# Amplifier.net
KiCad netlist of a schematic drawn in Altium Designer
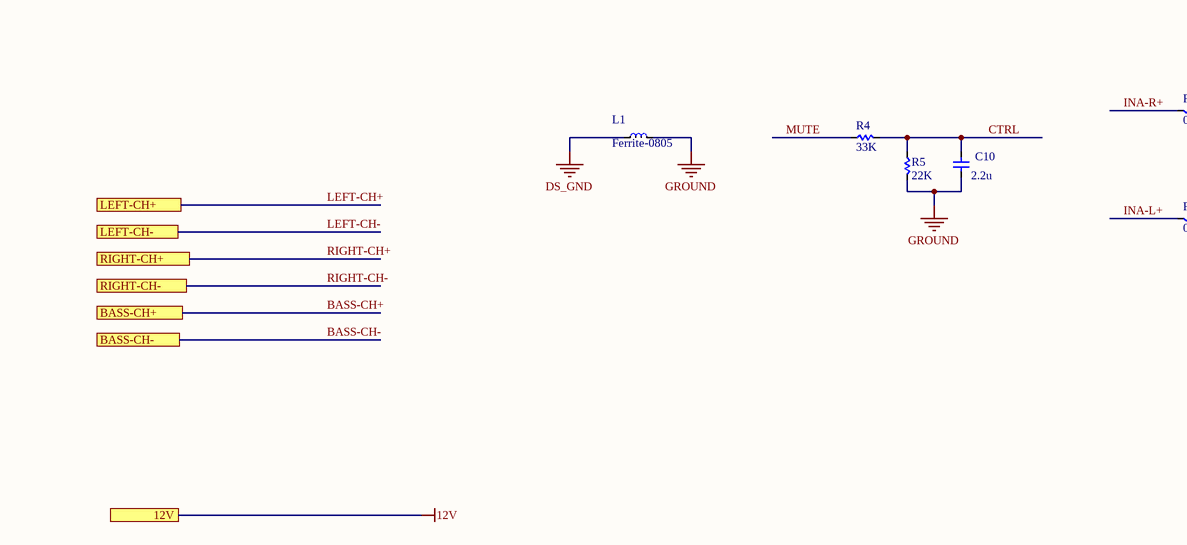
[diagram p0: Amplifier.SchDoc, top left]
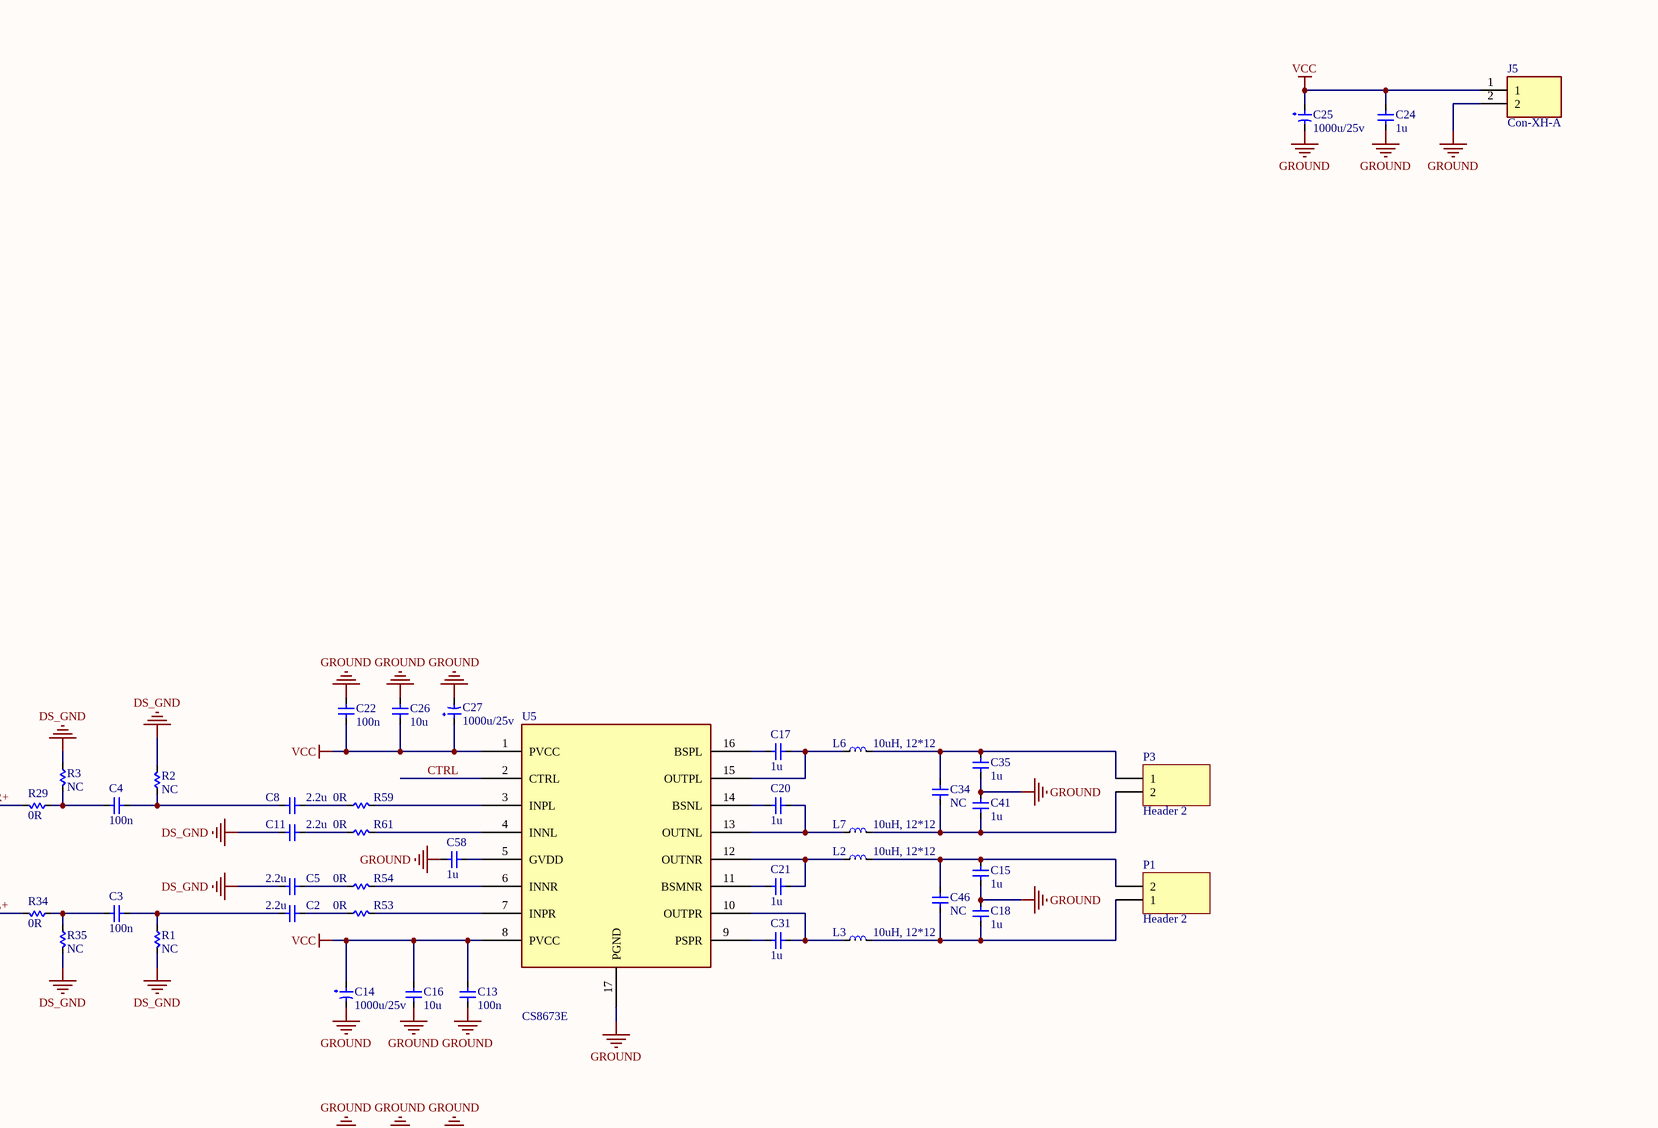
[diagram p1: Amplifier.SchDoc, top right]
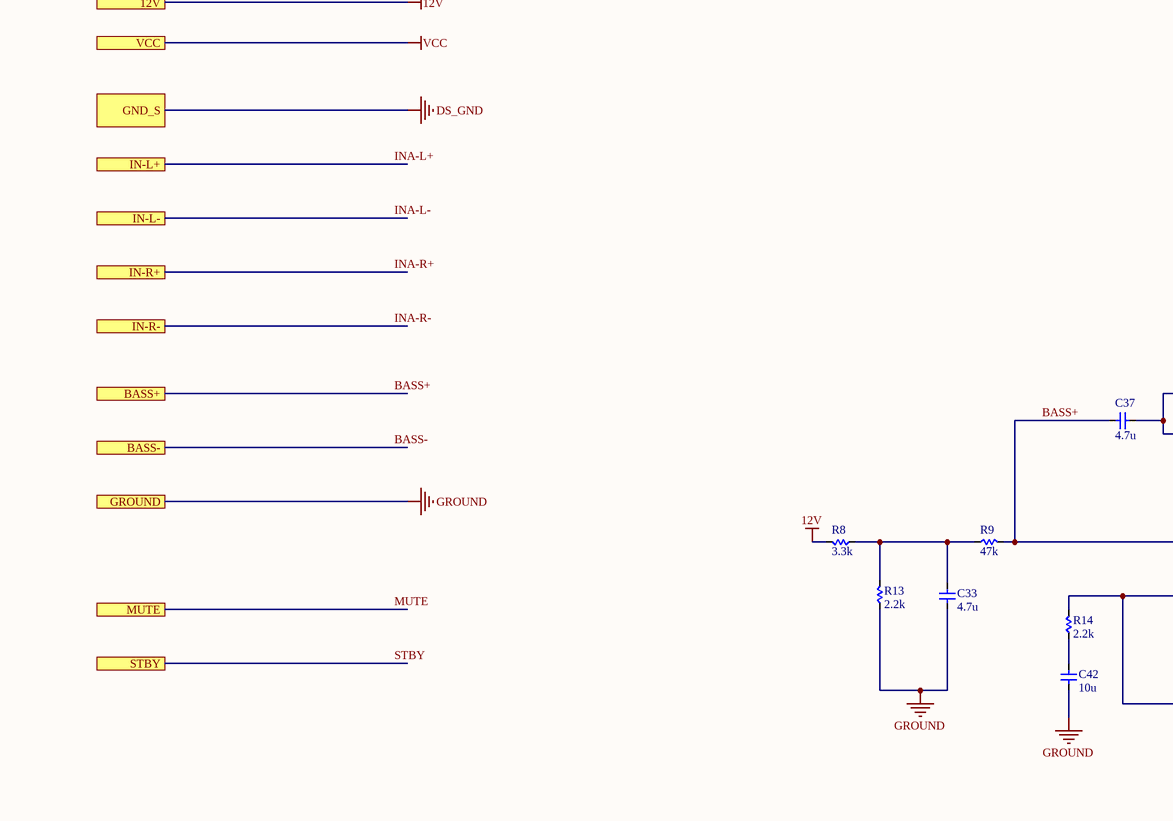
[diagram p2: Amplifier.SchDoc, bottom left]
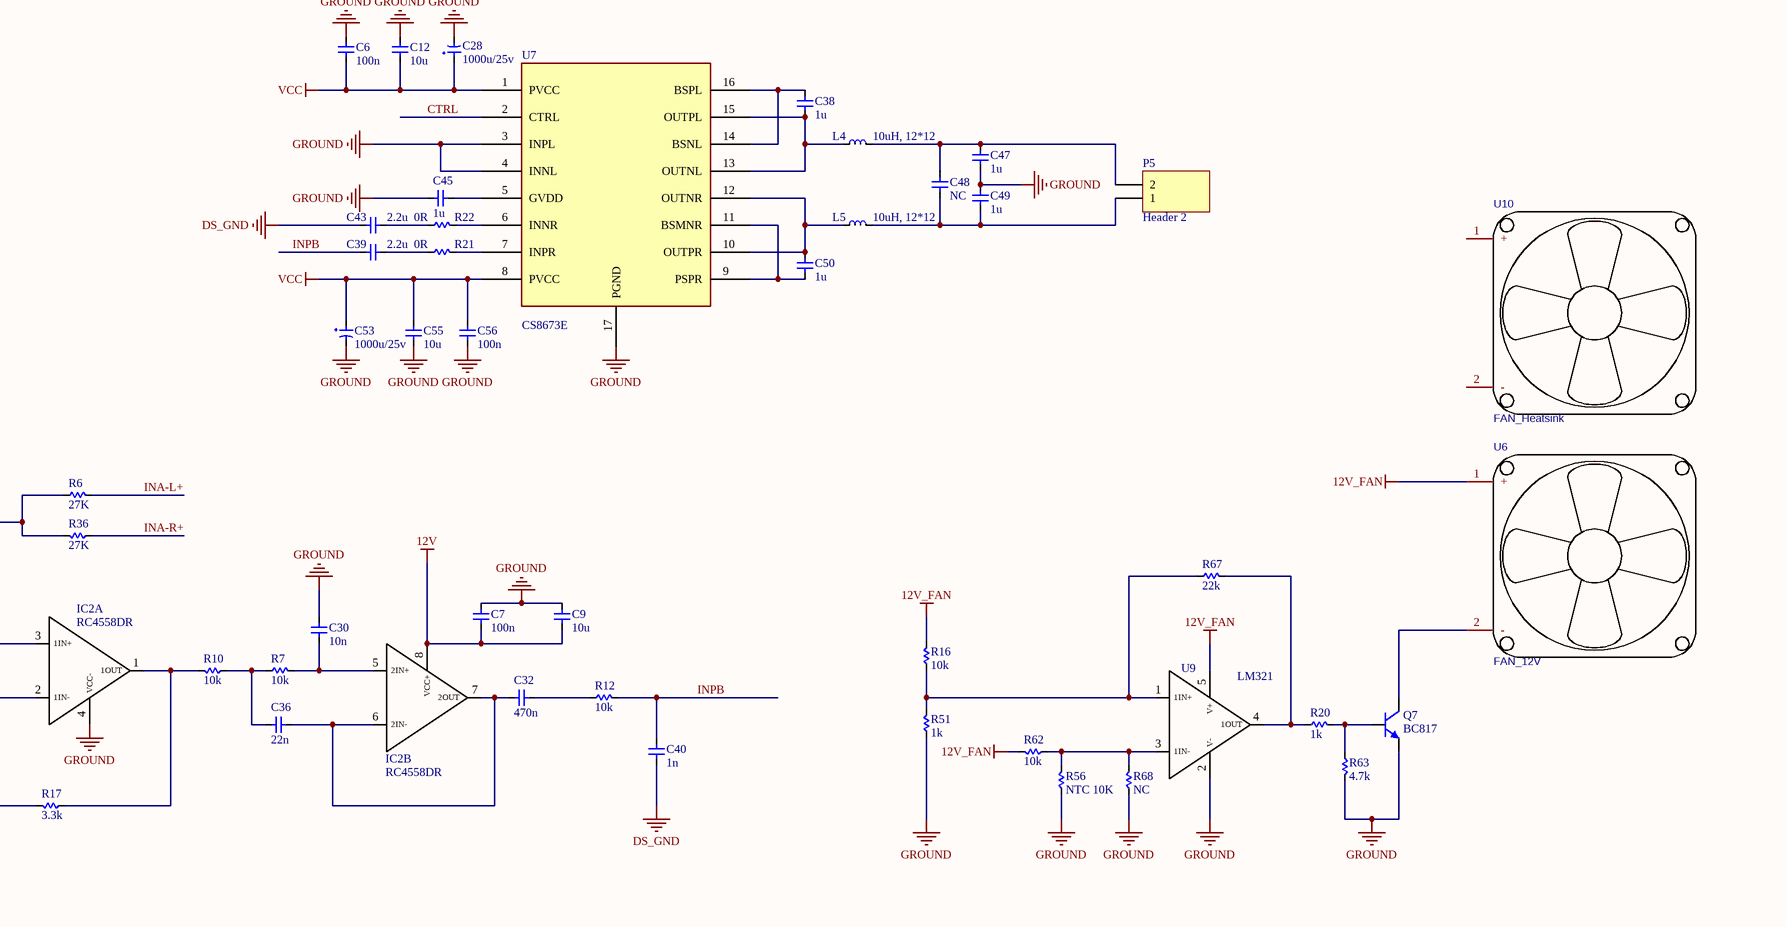
[diagram p3: Amplifier.SchDoc, bottom right]

(export (version "E")
  (design (tool "Eeschema 10.0.6"))
  (components
    (comp (ref "C2")
      (value "2.2u")
      (footprint "cap0603")
      (description "Capacitor 0603")
      (fields (field (name "PUBLISHER") "Altium Limited"))
      (libsource (lib "mylib1") (part "Cap 0603"))
    )
    (comp (ref "C3")
      (value "100n")
      (footprint "cap0603")
      (description "Capacitor 0603")
      (fields (field (name "PUBLISHER") "Altium Limited"))
      (libsource (lib "mylib") (part "Cap 0603"))
    )
    (comp (ref "C4")
      (value "100n")
      (footprint "cap0603")
      (description "Capacitor 0603")
      (fields (field (name "PUBLISHER") "Altium Limited"))
      (libsource (lib "mylib") (part "Cap 0603"))
    )
    (comp (ref "C5")
      (value "2.2u")
      (footprint "cap0603")
      (description "Capacitor 0603")
      (fields (field (name "PUBLISHER") "Altium Limited"))
      (libsource (lib "mylib1") (part "Cap 0603"))
    )
    (comp (ref "C6")
      (value "100n")
      (footprint "cap0603")
      (description "Capacitor 0603")
      (fields (field (name "PUBLISHER") "Altium Limited"))
      (libsource (lib "mylib1") (part "Cap 0603"))
    )
    (comp (ref "C7")
      (value "100n")
      (footprint "cap0603")
      (description "Capacitor 0603")
      (fields (field (name "PUBLISHER") "Altium Limited"))
      (libsource (lib "mylib1") (part "Cap 0603"))
    )
    (comp (ref "C8")
      (value "2.2u")
      (footprint "cap0603")
      (description "Capacitor 0603")
      (fields (field (name "PUBLISHER") "Altium Limited"))
      (libsource (lib "mylib1") (part "Cap 0603"))
    )
    (comp (ref "C9")
      (value "10u")
      (footprint "CAP 0805")
      (description "Capacitor 0805")
      (fields (field (name "PUBLISHER") "Altium Limited"))
      (libsource (lib "Amin-Library") (part "Cap 0805"))
    )
    (comp (ref "C10")
      (value "2.2u")
      (footprint "cap0603")
      (description "Capacitor 0603")
      (fields (field (name "PUBLISHER") "Altium Limited"))
      (libsource (lib "mylib") (part "Cap 0603"))
    )
    (comp (ref "C11")
      (value "2.2u")
      (footprint "cap0603")
      (description "Capacitor 0603")
      (fields (field (name "PUBLISHER") "Altium Limited"))
      (libsource (lib "mylib1") (part "Cap 0603"))
    )
    (comp (ref "C12")
      (value "10u")
      (footprint "CAP 0805")
      (description "Capacitor 0805")
      (fields (field (name "PUBLISHER") "Altium Limited"))
      (libsource (lib "Amin-Library") (part "Cap 0805"))
    )
    (comp (ref "C13")
      (value "100n")
      (footprint "cap0603")
      (description "Capacitor 0603")
      (fields (field (name "PUBLISHER") "Altium Limited"))
      (libsource (lib "mylib1") (part "Cap 0603"))
    )
    (comp (ref "C14")
      (value "1000u/25v")
      (footprint "CAP DIP 10*13")
      (description "2200ÂµF 50V Aluminum Electrolytic Capacitors Radial, Can 1000 Hrs @ 105Â°C")
      (fields (field (name "MF") "Nichicon") (field (name "MP") "UVZ1H222MHD"))
      (libsource (lib "") (part "capacitor dip 10*13_1"))
    )
    (comp (ref "C15")
      (value "1u")
      (footprint "CAP 0805")
      (description "Capacitor 0805")
      (fields (field (name "PUBLISHER") "Altium Limited"))
      (libsource (lib "Amin-Library") (part "Cap 0805"))
    )
    (comp (ref "C16")
      (value "10u")
      (footprint "CAP 0805")
      (description "Capacitor 0805")
      (fields (field (name "PUBLISHER") "Altium Limited"))
      (libsource (lib "Amin-Library") (part "Cap 0805"))
    )
    (comp (ref "C17")
      (value "1u")
      (footprint "CAP 0805")
      (description "Capacitor 0805")
      (fields (field (name "PUBLISHER") "Altium Limited"))
      (libsource (lib "Amin-Library") (part "Cap 0805"))
    )
    (comp (ref "C18")
      (value "1u")
      (footprint "CAP 0805")
      (description "Capacitor 0805")
      (fields (field (name "PUBLISHER") "Altium Limited"))
      (libsource (lib "Amin-Library") (part "Cap 0805"))
    )
    (comp (ref "C20")
      (value "1u")
      (footprint "CAP 0805")
      (description "Capacitor 0805")
      (fields (field (name "PUBLISHER") "Altium Limited"))
      (libsource (lib "Amin-Library") (part "Cap 0805"))
    )
    (comp (ref "C21")
      (value "1u")
      (footprint "CAP 0805")
      (description "Capacitor 0805")
      (fields (field (name "PUBLISHER") "Altium Limited"))
      (libsource (lib "Amin-Library") (part "Cap 0805"))
    )
    (comp (ref "C22")
      (value "100n")
      (footprint "cap0603")
      (description "Capacitor 0603")
      (fields (field (name "PUBLISHER") "Altium Limited"))
      (libsource (lib "mylib1") (part "Cap 0603"))
    )
    (comp (ref "C24")
      (value "1u")
      (footprint "cap0603")
      (description "Capacitor 0603")
      (fields (field (name "PUBLISHER") "Altium Limited"))
      (libsource (lib "mylib1") (part "Cap 0603"))
    )
    (comp (ref "C25")
      (value "1000u/25v")
      (footprint "CAP DIP 10*13")
      (description "2200ÂµF 50V Aluminum Electrolytic Capacitors Radial, Can 1000 Hrs @ 105Â°C")
      (fields (field (name "MF") "Nichicon") (field (name "MP") "UVZ1H222MHD"))
      (libsource (lib "") (part "capacitor dip 10*13_1"))
    )
    (comp (ref "C26")
      (value "10u")
      (footprint "CAP 0805")
      (description "Capacitor 0805")
      (fields (field (name "PUBLISHER") "Altium Limited"))
      (libsource (lib "Amin-Library") (part "Cap 0805"))
    )
    (comp (ref "C27")
      (value "1000u/25v")
      (footprint "CAP DIP 10*13")
      (description "2200ÂµF 50V Aluminum Electrolytic Capacitors Radial, Can 1000 Hrs @ 105Â°C")
      (fields (field (name "MF") "Nichicon") (field (name "MP") "UVZ1H222MHD"))
      (libsource (lib "mylib1") (part "capacitor dip 10*13"))
    )
    (comp (ref "C28")
      (value "1000u/25v")
      (footprint "CAP DIP 10*13")
      (description "2200ÂµF 50V Aluminum Electrolytic Capacitors Radial, Can 1000 Hrs @ 105Â°C")
      (fields (field (name "MF") "Nichicon") (field (name "MP") "UVZ1H222MHD"))
      (libsource (lib "mylib1") (part "capacitor dip 10*13"))
    )
    (comp (ref "C30")
      (value "10n")
      (footprint "cap0603")
      (description "Capacitor 0603")
      (fields (field (name "PUBLISHER") "Altium Limited"))
      (libsource (lib "mylib1") (part "Cap 0603"))
    )
    (comp (ref "C31")
      (value "1u")
      (footprint "CAP 0805")
      (description "Capacitor 0805")
      (fields (field (name "PUBLISHER") "Altium Limited"))
      (libsource (lib "Amin-Library") (part "Cap 0805"))
    )
    (comp (ref "C32")
      (value "470n")
      (footprint "cap0603")
      (description "Capacitor 0603")
      (fields (field (name "PUBLISHER") "Altium Limited"))
      (libsource (lib "mylib1") (part "Cap 0603"))
    )
    (comp (ref "C33")
      (value "4.7u")
      (footprint "cap0603")
      (description "Capacitor 0603")
      (fields (field (name "PUBLISHER") "Altium Limited"))
      (libsource (lib "mylib") (part "Cap 0603"))
    )
    (comp (ref "C34")
      (value "NC")
      (footprint "CAP 0805")
      (description "Capacitor 0805")
      (fields (field (name "PUBLISHER") "Altium Limited"))
      (libsource (lib "Amin-Library") (part "Cap 0805"))
    )
    (comp (ref "C35")
      (value "1u")
      (footprint "CAP 0805")
      (description "Capacitor 0805")
      (fields (field (name "PUBLISHER") "Altium Limited"))
      (libsource (lib "Amin-Library") (part "Cap 0805"))
    )
    (comp (ref "C36")
      (value "22n")
      (footprint "cap0603")
      (description "Capacitor 0603")
      (fields (field (name "PUBLISHER") "Altium Limited"))
      (libsource (lib "mylib1") (part "Cap 0603"))
    )
    (comp (ref "C37")
      (value "4.7u")
      (footprint "cap0603")
      (description "Capacitor 0603")
      (fields (field (name "PUBLISHER") "Altium Limited"))
      (libsource (lib "mylib") (part "Cap 0603"))
    )
    (comp (ref "C38")
      (value "1u")
      (footprint "CAP 0805")
      (description "Capacitor 0805")
      (fields (field (name "PUBLISHER") "Altium Limited"))
      (libsource (lib "Amin-Library") (part "Cap 0805"))
    )
    (comp (ref "C39")
      (value "2.2u")
      (footprint "cap0603")
      (description "Capacitor 0603")
      (fields (field (name "PUBLISHER") "Altium Limited"))
      (libsource (lib "mylib1") (part "Cap 0603"))
    )
    (comp (ref "C40")
      (value "1n")
      (footprint "cap0603")
      (description "Capacitor 0603")
      (fields (field (name "PUBLISHER") "Altium Limited"))
      (libsource (lib "mylib1") (part "Cap 0603"))
    )
    (comp (ref "C41")
      (value "1u")
      (footprint "CAP 0805")
      (description "Capacitor 0805")
      (fields (field (name "PUBLISHER") "Altium Limited"))
      (libsource (lib "Amin-Library") (part "Cap 0805"))
    )
    (comp (ref "C42")
      (value "10u")
      (footprint "CAP 1206")
      (description "Capacitor 1206")
      (fields (field (name "PUBLISHER") "Altium Limited"))
      (libsource (lib "mylib") (part "Cap 1206"))
    )
    (comp (ref "C43")
      (value "2.2u")
      (footprint "cap0603")
      (description "Capacitor 0603")
      (fields (field (name "PUBLISHER") "Altium Limited"))
      (libsource (lib "mylib1") (part "Cap 0603"))
    )
    (comp (ref "C45")
      (value "1u")
      (footprint "cap0603")
      (description "Capacitor 0603")
      (fields (field (name "PUBLISHER") "Altium Limited"))
      (libsource (lib "mylib1") (part "Cap 0603"))
    )
    (comp (ref "C46")
      (value "NC")
      (footprint "CAP 0805")
      (description "Capacitor 0805")
      (fields (field (name "PUBLISHER") "Altium Limited"))
      (libsource (lib "Amin-Library") (part "Cap 0805"))
    )
    (comp (ref "C47")
      (value "1u")
      (footprint "CAP 0805")
      (description "Capacitor 0805")
      (fields (field (name "PUBLISHER") "Altium Limited"))
      (libsource (lib "Amin-Library") (part "Cap 0805"))
    )
    (comp (ref "C48")
      (value "NC")
      (footprint "CAP 0805")
      (description "Capacitor 0805")
      (fields (field (name "PUBLISHER") "Altium Limited"))
      (libsource (lib "Amin-Library") (part "Cap 0805"))
    )
    (comp (ref "C49")
      (value "1u")
      (footprint "CAP 0805")
      (description "Capacitor 0805")
      (fields (field (name "PUBLISHER") "Altium Limited"))
      (libsource (lib "Amin-Library") (part "Cap 0805"))
    )
    (comp (ref "C50")
      (value "1u")
      (footprint "CAP 0805")
      (description "Capacitor 0805")
      (fields (field (name "PUBLISHER") "Altium Limited"))
      (libsource (lib "Amin-Library") (part "Cap 0805"))
    )
    (comp (ref "C53")
      (value "1000u/25v")
      (footprint "CAP DIP 10*13")
      (description "2200ÂµF 50V Aluminum Electrolytic Capacitors Radial, Can 1000 Hrs @ 105Â°C")
      (fields (field (name "MF") "Nichicon") (field (name "MP") "UVZ1H222MHD"))
      (libsource (lib "") (part "capacitor dip 10*13_1"))
    )
    (comp (ref "C55")
      (value "10u")
      (footprint "CAP 0805")
      (description "Capacitor 0805")
      (fields (field (name "PUBLISHER") "Altium Limited"))
      (libsource (lib "Amin-Library") (part "Cap 0805"))
    )
    (comp (ref "C56")
      (value "100n")
      (footprint "cap0603")
      (description "Capacitor 0603")
      (fields (field (name "PUBLISHER") "Altium Limited"))
      (libsource (lib "mylib1") (part "Cap 0603"))
    )
    (comp (ref "C58")
      (value "1u")
      (footprint "cap0603")
      (description "Capacitor 0603")
      (fields (field (name "PUBLISHER") "Altium Limited"))
      (libsource (lib "mylib1") (part "Cap 0603"))
    )
    (comp (ref "IC2")
      (value "RC4558DR")
      (footprint "RC4558")
      (description "Integrated Circuit SOIC 8")
      (fields (field (name "MOUSER PART NUMBER") "595-RC4558DR"))
      (libsource (lib "STM32F103C8T6") (part "RC4558DR"))
    )
    (comp (ref "J5")
      (value "Con-XH-A")
      (footprint "Con-JST_B2B-XH-A")
      (description "Connector Header Through Hole 2 position 0.098 _2.50mm_")
      (fields (field (name "MP") "B2B-XH-A_LF__SN_") (field (name "MF") "JST Sales"))
      (libsource (lib "Amin-Library") (part "Con-B2B-XH-A"))
    )
    (comp (ref "L1")
      (value "Ferrite-0805")
      (footprint "Ferrite-0805")
      (description "BLM Series 0805 330 Ohm 400 mA 0.58 Ohm DCR Surface Mount Ferrite Bead")
      (fields (field (name "MF") "Murata") (field (name "MP") "BLM18BB331SN1D"))
      (libsource (lib "mylib") (part "Ferrite _0805"))
    )
    (comp (ref "L2")
      (value "10uH, 12*12")
      (footprint "inductor 12*12")
      (description "Inductor round 12*12")
      (fields (field (name "MP") "DR127-330-R") (field (name "MF") "Eaton"))
      (libsource (lib "Amin-Library") (part "INDUCTOR 12*12"))
    )
    (comp (ref "L3")
      (value "10uH, 12*12")
      (footprint "inductor 12*12")
      (description "Inductor round 12*12")
      (fields (field (name "MP") "DR127-330-R") (field (name "MF") "Eaton"))
      (libsource (lib "Amin-Library") (part "INDUCTOR 12*12"))
    )
    (comp (ref "L4")
      (value "10uH, 12*12")
      (footprint "inductor 12*12")
      (description "Inductor round 12*12")
      (fields (field (name "MP") "DR127-330-R") (field (name "MF") "Eaton"))
      (libsource (lib "Amin-Library") (part "INDUCTOR 12*12"))
    )
    (comp (ref "L5")
      (value "10uH, 12*12")
      (footprint "inductor 12*12")
      (description "Inductor round 12*12")
      (fields (field (name "MP") "DR127-330-R") (field (name "MF") "Eaton"))
      (libsource (lib "Amin-Library") (part "INDUCTOR 12*12"))
    )
    (comp (ref "L6")
      (value "10uH, 12*12")
      (footprint "inductor 12*12")
      (description "Inductor round 12*12")
      (fields (field (name "MP") "DR127-330-R") (field (name "MF") "Eaton"))
      (libsource (lib "Amin-Library") (part "INDUCTOR 12*12"))
    )
    (comp (ref "L7")
      (value "10uH, 12*12")
      (footprint "inductor 12*12")
      (description "Inductor round 12*12")
      (fields (field (name "MP") "DR127-330-R") (field (name "MF") "Eaton"))
      (libsource (lib "Amin-Library") (part "INDUCTOR 12*12"))
    )
    (comp (ref "P1")
      (value "Header 2")
      (footprint "CONN-PHOENIX-5.08")
      (description "Phoenix Connector 5.08")
      (fields (field (name "PUBLISHER") "Altium Limited"))
      (libsource (lib "") (part "CONN-Phoenix-5.08_1"))
    )
    (comp (ref "P3")
      (value "Header 2")
      (footprint "CONN-PHOENIX-5.08")
      (description "Phoenix Connector 5.08")
      (fields (field (name "PUBLISHER") "Altium Limited"))
      (libsource (lib "Amin-Library") (part "CONN-Phoenix-5.08"))
    )
    (comp (ref "P5")
      (value "Header 2")
      (footprint "CONN-PHOENIX-5.08")
      (description "Phoenix Connector 5.08")
      (fields (field (name "PUBLISHER") "Altium Limited"))
      (libsource (lib "") (part "CONN-Phoenix-5.08_1"))
    )
    (comp (ref "Q7")
      (value "BC817")
      (footprint "BC817")
      (description "NPN General Purpose Amplifier BJT")
      (fields (field (name "PUBLISHER") "Altium Limited"))
      (libsource (lib "Amin-Library") (part "BC817"))
    )
    (comp (ref "R1")
      (value "NC")
      (footprint "RES-0603")
      (description "Resistor 0603")
      (fields (field (name "PUBLISHER") "Altium Limited"))
      (libsource (lib "mylib1") (part "Res 0603"))
    )
    (comp (ref "R2")
      (value "NC")
      (footprint "RES-0603")
      (description "Resistor 0603")
      (fields (field (name "PUBLISHER") "Altium Limited"))
      (libsource (lib "mylib1") (part "Res 0603"))
    )
    (comp (ref "R3")
      (value "NC")
      (footprint "RES-0603")
      (description "Resistor 0603")
      (fields (field (name "PUBLISHER") "Altium Limited"))
      (libsource (lib "mylib1") (part "Res 0603"))
    )
    (comp (ref "R4")
      (value "33K")
      (footprint "RES-0603")
      (description "Resistor 0603")
      (fields (field (name "PUBLISHER") "Altium Limited"))
      (libsource (lib "mylib1") (part "Res 0603"))
    )
    (comp (ref "R5")
      (value "22K")
      (footprint "RES-0603")
      (description "Resistor 0603")
      (fields (field (name "PUBLISHER") "Altium Limited"))
      (libsource (lib "mylib1") (part "Res 0603"))
    )
    (comp (ref "R6")
      (value "27K")
      (footprint "RES-0603")
      (description "Resistor 0603")
      (fields (field (name "PUBLISHER") "Altium Limited"))
      (libsource (lib "mylib1") (part "Res 0603"))
    )
    (comp (ref "R7")
      (value "10k")
      (footprint "RES-0603")
      (description "Resistor 0603")
      (fields (field (name "PUBLISHER") "Altium Limited"))
      (libsource (lib "mylib1") (part "Res 0603"))
    )
    (comp (ref "R8")
      (value "3.3k")
      (footprint "RES-0603")
      (description "Resistor 0603")
      (fields (field (name "PUBLISHER") "Altium Limited"))
      (libsource (lib "mylib1") (part "Res 0603"))
    )
    (comp (ref "R9")
      (value "47k")
      (footprint "RES-0603")
      (description "Resistor 0603")
      (fields (field (name "PUBLISHER") "Altium Limited"))
      (libsource (lib "mylib1") (part "Res 0603"))
    )
    (comp (ref "R10")
      (value "10k")
      (footprint "RES-0603")
      (description "Resistor 0603")
      (fields (field (name "PUBLISHER") "Altium Limited"))
      (libsource (lib "mylib1") (part "Res 0603"))
    )
    (comp (ref "R12")
      (value "10k")
      (footprint "RES-0603")
      (description "Resistor 0603")
      (fields (field (name "PUBLISHER") "Altium Limited"))
      (libsource (lib "mylib1") (part "Res 0603"))
    )
    (comp (ref "R13")
      (value "2.2k")
      (footprint "RES-0603")
      (description "Resistor 0603")
      (fields (field (name "PUBLISHER") "Altium Limited"))
      (libsource (lib "mylib1") (part "Res 0603"))
    )
    (comp (ref "R14")
      (value "2.2k")
      (footprint "RES-0603")
      (description "Resistor 0603")
      (fields (field (name "PUBLISHER") "Altium Limited"))
      (libsource (lib "mylib1") (part "Res 0603"))
    )
    (comp (ref "R16")
      (value "10k")
      (footprint "RES-0603")
      (description "Resistor 0603")
      (fields (field (name "PUBLISHER") "Altium Limited"))
      (libsource (lib "Amin-Library") (part "Res 0603"))
    )
    (comp (ref "R17")
      (value "3.3k")
      (footprint "RES-0603")
      (description "Resistor 0603")
      (fields (field (name "PUBLISHER") "Altium Limited"))
      (libsource (lib "mylib1") (part "Res 0603"))
    )
    (comp (ref "R20")
      (value "1k")
      (footprint "RES-0603")
      (description "Resistor 0603")
      (fields (field (name "PUBLISHER") "Altium Limited"))
      (libsource (lib "Amin-Library") (part "Res 0603"))
    )
    (comp (ref "R21")
      (value "0R")
      (footprint "RES-0603")
      (description "Resistor 0603")
      (fields (field (name "PUBLISHER") "Altium Limited"))
      (libsource (lib "Amin-Library") (part "Res 0603"))
    )
    (comp (ref "R22")
      (value "0R")
      (footprint "RES-0603")
      (description "Resistor 0603")
      (fields (field (name "PUBLISHER") "Altium Limited"))
      (libsource (lib "Amin-Library") (part "Res 0603"))
    )
    (comp (ref "R29")
      (value "0R")
      (footprint "RES-0603")
      (description "Resistor 0603")
      (fields (field (name "PUBLISHER") "Altium Limited"))
      (libsource (lib "mylib1") (part "Res 0603"))
    )
    (comp (ref "R34")
      (value "0R")
      (footprint "RES-0603")
      (description "Resistor 0603")
      (fields (field (name "PUBLISHER") "Altium Limited"))
      (libsource (lib "mylib1") (part "Res 0603"))
    )
    (comp (ref "R35")
      (value "NC")
      (footprint "RES-0603")
      (description "Resistor 0603")
      (fields (field (name "PUBLISHER") "Altium Limited"))
      (libsource (lib "mylib1") (part "Res 0603"))
    )
    (comp (ref "R36")
      (value "27K")
      (footprint "RES-0603")
      (description "Resistor 0603")
      (fields (field (name "PUBLISHER") "Altium Limited"))
      (libsource (lib "mylib1") (part "Res 0603"))
    )
    (comp (ref "R51")
      (value "1k")
      (footprint "RES-0603")
      (description "Resistor 0603")
      (fields (field (name "PUBLISHER") "Altium Limited"))
      (libsource (lib "Amin-Library") (part "Res 0603"))
    )
    (comp (ref "R53")
      (value "0R")
      (footprint "RES-0603")
      (description "Resistor 0603")
      (fields (field (name "PUBLISHER") "Altium Limited"))
      (libsource (lib "Amin-Library") (part "Res 0603"))
    )
    (comp (ref "R54")
      (value "0R")
      (footprint "RES-0603")
      (description "Resistor 0603")
      (fields (field (name "PUBLISHER") "Altium Limited"))
      (libsource (lib "Amin-Library") (part "Res 0603"))
    )
    (comp (ref "R56")
      (value "NTC 10K")
      (footprint "RES-0805")
      (description "resistor 0805")
      (libsource (lib "Amin-Library") (part "Res 0805"))
    )
    (comp (ref "R59")
      (value "0R")
      (footprint "RES-0603")
      (description "Resistor 0603")
      (fields (field (name "PUBLISHER") "Altium Limited"))
      (libsource (lib "Amin-Library") (part "Res 0603"))
    )
    (comp (ref "R61")
      (value "0R")
      (footprint "RES-0603")
      (description "Resistor 0603")
      (fields (field (name "PUBLISHER") "Altium Limited"))
      (libsource (lib "Amin-Library") (part "Res 0603"))
    )
    (comp (ref "R62")
      (value "10k")
      (footprint "RES-0603")
      (description "Resistor 0603")
      (fields (field (name "PUBLISHER") "Altium Limited"))
      (libsource (lib "Amin-Library") (part "Res 0603"))
    )
    (comp (ref "R63")
      (value "4.7k")
      (footprint "RES-0603")
      (description "Resistor 0603")
      (fields (field (name "PUBLISHER") "Altium Limited"))
      (libsource (lib "Amin-Library") (part "Res 0603"))
    )
    (comp (ref "R67")
      (value "22k")
      (footprint "RES-0603")
      (description "Resistor 0603")
      (fields (field (name "PUBLISHER") "Altium Limited"))
      (libsource (lib "Amin-Library") (part "Res 0603"))
    )
    (comp (ref "R68")
      (value "NC")
      (footprint "RES-0805")
      (description "resistor 0805")
      (libsource (lib "Amin-Library") (part "Res 0805"))
    )
    (comp (ref "U5")
      (value "CS8673E")
      (footprint "CS8673E")
      (description "AB/D 2X40W BTL & 80W PBTL ESOP16")
      (fields
        (field (name "MANUFACTURER_PART_NUMBER") "CS8679E")
        (field (name "MOUSER PART NUMBER") "511-TDA7491HV13TR")
      )
      (libsource (lib "Amin-Library") (part "CS8673E"))
    )
    (comp (ref "U6")
      (value "FAN_12V")
      (footprint "FAN_Connector XH")
      (description "FAN 12V 40*40*10mm . XH Connector")
      (fields (field (name "MANUFACTURER PART") "?") (field (name "CONTRIBUTOR") "novasilisko"))
      (libsource (lib "Amin-Library_S2") (part "FAN_12V"))
    )
    (comp (ref "U7")
      (value "CS8673E")
      (footprint "CS8673E")
      (description "AB/D 2X40W BTL & 80W PBTL ESOP16")
      (fields
        (field (name "MANUFACTURER_PART_NUMBER") "CS8679E")
        (field (name "MOUSER PART NUMBER") "511-TDA7491HV13TR")
      )
      (libsource (lib "Amin-Library") (part "CS8673E"))
    )
    (comp (ref "U9")
      (value "LM321")
      (footprint "LM321")
      (description "Operational Amplifier 5-SOT-23")
      (fields (field (name "MP") "OPA354AIDBVT") (field (name "DIGI-KEY_PART_NUMBER") "296-13033-1-ND"))
      (libsource (lib "Amin-Library") (part "LM321"))
    )
    (comp (ref "U10")
      (value "FAN_Heatsink")
      (footprint "FAN_Heatsink")
      (description "55mm Aluminum Heatsink with Cooling Fan")
      (fields (field (name "MANUFACTURER PART") "?") (field (name "CONTRIBUTOR") "novasilisko"))
      (libsource (lib "Amin-Library") (part "FAN_Heatsink"))
    )
  )
  (nets
    (net (code "1") (name "/BASS+") (class "Default")
      (node (ref "C37") (pin "1") (pinfunction "1_1") (pintype "passive"))
      (node (ref "IC2") (pin "3") (pinfunction "1IN+_3") (pintype "passive"))
      (node (ref "R9") (pin "2") (pinfunction "2_2") (pintype "passive"))
    )
    (net (code "5") (name "/CTRL") (class "Default")
      (node (ref "C10") (pin "2") (pinfunction "2_2") (pintype "passive"))
      (node (ref "R4") (pin "2") (pinfunction "2_2") (pintype "passive"))
      (node (ref "R5") (pin "1") (pinfunction "1_1") (pintype "passive"))
      (node (ref "U5") (pin "2") (pinfunction "CTRL_2") (pintype "passive"))
      (node (ref "U7") (pin "2") (pinfunction "CTRL_2") (pintype "passive"))
    )
    (net (code "6") (name "/INA-L+") (class "Default")
      (node (ref "R34") (pin "2") (pinfunction "2_2") (pintype "passive"))
      (node (ref "R6") (pin "2") (pinfunction "2_2") (pintype "passive"))
    )
    (net (code "8") (name "/INA-R+") (class "Default")
      (node (ref "R29") (pin "2") (pinfunction "2_2") (pintype "passive"))
      (node (ref "R36") (pin "1") (pinfunction "1_1") (pintype "passive"))
    )
    (net (code "10") (name "/INPB") (class "Default")
      (node (ref "C39") (pin "2") (pinfunction "2_2") (pintype "passive"))
      (node (ref "C40") (pin "2") (pinfunction "2_2") (pintype "passive"))
      (node (ref "R12") (pin "2") (pinfunction "2_2") (pintype "passive"))
    )
    (net (code "13") (name "/MUTE") (class "Default")
      (node (ref "R4") (pin "1") (pinfunction "1_1") (pintype "passive"))
    )
    (net (code "17") (name "12V") (class "Default")
      (node (ref "C7") (pin "2") (pinfunction "2_2") (pintype "passive"))
      (node (ref "C9") (pin "2") (pinfunction "2_2") (pintype "passive"))
      (node (ref "IC2") (pin "8") (pinfunction "VCC+_8") (pintype "passive"))
      (node (ref "R8") (pin "2") (pinfunction "2_2") (pintype "passive"))
    )
    (net (code "18") (name "12V_FAN") (class "Default")
      (node (ref "R16") (pin "2") (pinfunction "2_2") (pintype "passive"))
      (node (ref "R62") (pin "2") (pinfunction "2_2") (pintype "passive"))
      (node (ref "U6") (pin "1") (pinfunction "+_1") (pintype "passive"))
      (node (ref "U9") (pin "5") (pinfunction "V+_5") (pintype "passive"))
    )
    (net (code "19") (name "DS_GND") (class "Default")
      (node (ref "C11") (pin "2") (pinfunction "2_2") (pintype "passive"))
      (node (ref "C40") (pin "1") (pinfunction "1_1") (pintype "passive"))
      (node (ref "C43") (pin "2") (pinfunction "2_2") (pintype "passive"))
      (node (ref "C5") (pin "2") (pinfunction "2_2") (pintype "passive"))
      (node (ref "L1") (pin "2") (pinfunction "2_2") (pintype "passive"))
      (node (ref "R1") (pin "2") (pinfunction "2_2") (pintype "passive"))
      (node (ref "R2") (pin "2") (pinfunction "2_2") (pintype "passive"))
      (node (ref "R3") (pin "1") (pinfunction "1_1") (pintype "passive"))
      (node (ref "R35") (pin "2") (pinfunction "2_2") (pintype "passive"))
    )
    (net (code "20") (name "GROUND") (class "Default")
      (node (ref "C10") (pin "1") (pinfunction "1_1") (pintype "passive"))
      (node (ref "C12") (pin "1") (pinfunction "1_1") (pintype "passive"))
      (node (ref "C13") (pin "2") (pinfunction "2_2") (pintype "passive"))
      (node (ref "C14") (pin "2") (pinfunction "NEG_2") (pintype "passive"))
      (node (ref "C15") (pin "1") (pinfunction "1_1") (pintype "passive"))
      (node (ref "C16") (pin "1") (pinfunction "1_1") (pintype "passive"))
      (node (ref "C18") (pin "2") (pinfunction "2_2") (pintype "passive"))
      (node (ref "C22") (pin "2") (pinfunction "2_2") (pintype "passive"))
      (node (ref "C24") (pin "2") (pinfunction "2_2") (pintype "passive"))
      (node (ref "C25") (pin "2") (pinfunction "NEG_2") (pintype "passive"))
      (node (ref "C26") (pin "1") (pinfunction "1_1") (pintype "passive"))
      (node (ref "C27") (pin "2") (pinfunction "NEG_2") (pintype "passive"))
      (node (ref "C28") (pin "2") (pinfunction "NEG_2") (pintype "passive"))
      (node (ref "C30") (pin "1") (pinfunction "1_1") (pintype "passive"))
      (node (ref "C33") (pin "1") (pinfunction "1_1") (pintype "passive"))
      (node (ref "C35") (pin "1") (pinfunction "1_1") (pintype "passive"))
      (node (ref "C41") (pin "2") (pinfunction "2_2") (pintype "passive"))
      (node (ref "C42") (pin "1") (pinfunction "1_1") (pintype "passive"))
      (node (ref "C45") (pin "1") (pinfunction "1_1") (pintype "passive"))
      (node (ref "C47") (pin "1") (pinfunction "1_1") (pintype "passive"))
      (node (ref "C49") (pin "2") (pinfunction "2_2") (pintype "passive"))
      (node (ref "C53") (pin "2") (pinfunction "NEG_2") (pintype "passive"))
      (node (ref "C55") (pin "1") (pinfunction "1_1") (pintype "passive"))
      (node (ref "C56") (pin "2") (pinfunction "2_2") (pintype "passive"))
      (node (ref "C58") (pin "1") (pinfunction "1_1") (pintype "passive"))
      (node (ref "C6") (pin "2") (pinfunction "2_2") (pintype "passive"))
      (node (ref "C7") (pin "1") (pinfunction "1_1") (pintype "passive"))
      (node (ref "C9") (pin "1") (pinfunction "1_1") (pintype "passive"))
      (node (ref "IC2") (pin "4") (pinfunction "VCC-_4") (pintype "passive"))
      (node (ref "J5") (pin "2") (pinfunction "2_2") (pintype "passive"))
      (node (ref "L1") (pin "1") (pinfunction "1_1") (pintype "passive"))
      (node (ref "Q7") (pin "2") (pinfunction "E_2") (pintype "passive"))
      (node (ref "R13") (pin "1") (pinfunction "1_1") (pintype "passive"))
      (node (ref "R5") (pin "2") (pinfunction "2_2") (pintype "passive"))
      (node (ref "R51") (pin "1") (pinfunction "1_1") (pintype "passive"))
      (node (ref "R56") (pin "1") (pinfunction "1_1") (pintype "passive"))
      (node (ref "R63") (pin "2") (pinfunction "2_2") (pintype "passive"))
      (node (ref "R68") (pin "1") (pinfunction "1_1") (pintype "passive"))
      (node (ref "U5") (pin "17") (pinfunction "PGND_17") (pintype "passive"))
      (node (ref "U7") (pin "17") (pinfunction "PGND_17") (pintype "passive"))
      (node (ref "U7") (pin "3") (pinfunction "INPL_3") (pintype "passive"))
      (node (ref "U7") (pin "4") (pinfunction "INNL_4") (pintype "passive"))
      (node (ref "U9") (pin "2") (pinfunction "V-_2") (pintype "passive"))
    )
    (net (code "21") (name "Net-(C2-Pad1)") (class "Default")
      (node (ref "C2") (pin "1") (pinfunction "1_1") (pintype "passive"))
      (node (ref "C3") (pin "1") (pinfunction "1_1") (pintype "passive"))
      (node (ref "R1") (pin "1") (pinfunction "1_1") (pintype "passive"))
    )
    (net (code "22") (name "Net-(C2-Pad2)") (class "Default")
      (node (ref "C2") (pin "2") (pinfunction "2_2") (pintype "passive"))
      (node (ref "R53") (pin "1") (pinfunction "1_1") (pintype "passive"))
    )
    (net (code "23") (name "Net-(C3-Pad2)") (class "Default")
      (node (ref "C3") (pin "2") (pinfunction "2_2") (pintype "passive"))
      (node (ref "R34") (pin "1") (pinfunction "1_1") (pintype "passive"))
      (node (ref "R35") (pin "1") (pinfunction "1_1") (pintype "passive"))
    )
    (net (code "24") (name "Net-(C4-Pad1)") (class "Default")
      (node (ref "C4") (pin "1") (pinfunction "1_1") (pintype "passive"))
      (node (ref "C8") (pin "2") (pinfunction "2_2") (pintype "passive"))
      (node (ref "R2") (pin "1") (pinfunction "1_1") (pintype "passive"))
    )
    (net (code "25") (name "Net-(C4-Pad2)") (class "Default")
      (node (ref "C4") (pin "2") (pinfunction "2_2") (pintype "passive"))
      (node (ref "R29") (pin "1") (pinfunction "1_1") (pintype "passive"))
      (node (ref "R3") (pin "2") (pinfunction "2_2") (pintype "passive"))
    )
    (net (code "26") (name "Net-(C5-Pad1)") (class "Default")
      (node (ref "C5") (pin "1") (pinfunction "1_1") (pintype "passive"))
      (node (ref "R54") (pin "1") (pinfunction "1_1") (pintype "passive"))
    )
    (net (code "27") (name "Net-(C8-Pad1)") (class "Default")
      (node (ref "C8") (pin "1") (pinfunction "1_1") (pintype "passive"))
      (node (ref "R59") (pin "1") (pinfunction "1_1") (pintype "passive"))
    )
    (net (code "28") (name "Net-(C11-Pad1)") (class "Default")
      (node (ref "C11") (pin "1") (pinfunction "1_1") (pintype "passive"))
      (node (ref "R61") (pin "1") (pinfunction "1_1") (pintype "passive"))
    )
    (net (code "29") (name "Net-(C15-Pad2)") (class "Default")
      (node (ref "C15") (pin "2") (pinfunction "2_2") (pintype "passive"))
      (node (ref "C46") (pin "2") (pinfunction "2_2") (pintype "passive"))
      (node (ref "L2") (pin "1") (pinfunction "1_1") (pintype "passive"))
      (node (ref "P1") (pin "2") (pinfunction "2_2") (pintype "passive"))
    )
    (net (code "30") (name "Net-(C18-Pad1)") (class "Default")
      (node (ref "C18") (pin "1") (pinfunction "1_1") (pintype "passive"))
      (node (ref "C46") (pin "1") (pinfunction "1_1") (pintype "passive"))
      (node (ref "L3") (pin "1") (pinfunction "1_1") (pintype "passive"))
      (node (ref "P1") (pin "1") (pinfunction "1_1") (pintype "passive"))
    )
    (net (code "31") (name "Net-(C32-Pad2)") (class "Default")
      (node (ref "C32") (pin "2") (pinfunction "2_2") (pintype "passive"))
      (node (ref "R12") (pin "1") (pinfunction "1_1") (pintype "passive"))
    )
    (net (code "32") (name "Net-(C33-Pad2)") (class "Default")
      (node (ref "C33") (pin "2") (pinfunction "2_2") (pintype "passive"))
      (node (ref "R13") (pin "2") (pinfunction "2_2") (pintype "passive"))
      (node (ref "R8") (pin "1") (pinfunction "1_1") (pintype "passive"))
      (node (ref "R9") (pin "1") (pinfunction "1_1") (pintype "passive"))
    )
    (net (code "33") (name "Net-(C34-Pad1)") (class "Default")
      (node (ref "C34") (pin "1") (pinfunction "1_1") (pintype "passive"))
      (node (ref "C41") (pin "1") (pinfunction "1_1") (pintype "passive"))
      (node (ref "L7") (pin "1") (pinfunction "1_1") (pintype "passive"))
      (node (ref "P3") (pin "2") (pinfunction "2_2") (pintype "passive"))
    )
    (net (code "34") (name "Net-(C34-Pad2)") (class "Default")
      (node (ref "C34") (pin "2") (pinfunction "2_2") (pintype "passive"))
      (node (ref "C35") (pin "2") (pinfunction "2_2") (pintype "passive"))
      (node (ref "L6") (pin "1") (pinfunction "1_1") (pintype "passive"))
      (node (ref "P3") (pin "1") (pinfunction "1_1") (pintype "passive"))
    )
    (net (code "35") (name "Net-(C36-Pad2)") (class "Default")
      (node (ref "C36") (pin "2") (pinfunction "2_2") (pintype "passive"))
      (node (ref "R10") (pin "1") (pinfunction "1_1") (pintype "passive"))
      (node (ref "R7") (pin "1") (pinfunction "1_1") (pintype "passive"))
    )
    (net (code "36") (name "Net-(C37-Pad2)") (class "Default")
      (node (ref "C37") (pin "2") (pinfunction "2_2") (pintype "passive"))
      (node (ref "R36") (pin "2") (pinfunction "2_2") (pintype "passive"))
      (node (ref "R6") (pin "1") (pinfunction "1_1") (pintype "passive"))
    )
    (net (code "37") (name "Net-(C39-Pad1)") (class "Default")
      (node (ref "C39") (pin "1") (pinfunction "1_1") (pintype "passive"))
      (node (ref "R21") (pin "1") (pinfunction "1_1") (pintype "passive"))
    )
    (net (code "38") (name "Net-(C42-Pad2)") (class "Default")
      (node (ref "C42") (pin "2") (pinfunction "2_2") (pintype "passive"))
      (node (ref "R14") (pin "1") (pinfunction "1_1") (pintype "passive"))
    )
    (net (code "39") (name "Net-(C43-Pad1)") (class "Default")
      (node (ref "C43") (pin "1") (pinfunction "1_1") (pintype "passive"))
      (node (ref "R22") (pin "1") (pinfunction "1_1") (pintype "passive"))
    )
    (net (code "40") (name "Net-(C47-Pad2)") (class "Default")
      (node (ref "C47") (pin "2") (pinfunction "2_2") (pintype "passive"))
      (node (ref "C48") (pin "2") (pinfunction "2_2") (pintype "passive"))
      (node (ref "L4") (pin "1") (pinfunction "1_1") (pintype "passive"))
      (node (ref "P5") (pin "2") (pinfunction "2_2") (pintype "passive"))
    )
    (net (code "41") (name "Net-(C48-Pad1)") (class "Default")
      (node (ref "C48") (pin "1") (pinfunction "1_1") (pintype "passive"))
      (node (ref "C49") (pin "1") (pinfunction "1_1") (pintype "passive"))
      (node (ref "L5") (pin "1") (pinfunction "1_1") (pintype "passive"))
      (node (ref "P5") (pin "1") (pinfunction "1_1") (pintype "passive"))
    )
    (net (code "42") (name "Net-(IC2A-1IN-)") (class "Default")
      (node (ref "IC2") (pin "2") (pinfunction "1IN-_2") (pintype "passive"))
      (node (ref "R14") (pin "2") (pinfunction "2_2") (pintype "passive"))
      (node (ref "R17") (pin "2") (pinfunction "2_2") (pintype "passive"))
    )
    (net (code "43") (name "Net-(IC2A-1OUT)") (class "Default")
      (node (ref "IC2") (pin "1") (pinfunction "1OUT_1") (pintype "passive"))
      (node (ref "R10") (pin "2") (pinfunction "2_2") (pintype "passive"))
      (node (ref "R17") (pin "1") (pinfunction "1_1") (pintype "passive"))
    )
    (net (code "44") (name "Net-(IC2B-2IN+)") (class "Default")
      (node (ref "C30") (pin "2") (pinfunction "2_2") (pintype "passive"))
      (node (ref "IC2") (pin "5") (pinfunction "2IN+_5") (pintype "passive"))
      (node (ref "R7") (pin "2") (pinfunction "2_2") (pintype "passive"))
    )
    (net (code "45") (name "Net-(IC2B-2IN-)") (class "Default")
      (node (ref "C32") (pin "1") (pinfunction "1_1") (pintype "passive"))
      (node (ref "C36") (pin "1") (pinfunction "1_1") (pintype "passive"))
      (node (ref "IC2") (pin "6") (pinfunction "2IN-_6") (pintype "passive"))
      (node (ref "IC2") (pin "7") (pinfunction "2OUT_7") (pintype "passive"))
    )
    (net (code "46") (name "Net-(Q7-B)") (class "Default")
      (node (ref "Q7") (pin "1") (pinfunction "B_1") (pintype "passive"))
      (node (ref "R20") (pin "2") (pinfunction "2_2") (pintype "passive"))
      (node (ref "R63") (pin "1") (pinfunction "1_1") (pintype "passive"))
    )
    (net (code "47") (name "Net-(Q7-C)") (class "Default")
      (node (ref "Q7") (pin "3") (pinfunction "C_3") (pintype "passive"))
      (node (ref "U6") (pin "2") (pinfunction "-_2") (pintype "passive"))
    )
    (net (code "48") (name "Net-(U5-BSMNR)") (class "Default")
      (node (ref "C21") (pin "2") (pinfunction "2_2") (pintype "passive"))
      (node (ref "U5") (pin "11") (pinfunction "BSMNR_11") (pintype "passive"))
    )
    (net (code "49") (name "Net-(U5-BSNL)") (class "Default")
      (node (ref "C20") (pin "2") (pinfunction "2_2") (pintype "passive"))
      (node (ref "U5") (pin "14") (pinfunction "BSNL_14") (pintype "passive"))
    )
    (net (code "50") (name "Net-(U5-BSPL)") (class "Default")
      (node (ref "C17") (pin "2") (pinfunction "2_2") (pintype "passive"))
      (node (ref "U5") (pin "16") (pinfunction "BSPL_16") (pintype "passive"))
    )
    (net (code "51") (name "Net-(U5-GVDD)") (class "Default")
      (node (ref "C58") (pin "2") (pinfunction "2_2") (pintype "passive"))
      (node (ref "U5") (pin "5") (pinfunction "GVDD_5") (pintype "passive"))
    )
    (net (code "52") (name "Net-(U5-INNL)") (class "Default")
      (node (ref "R61") (pin "2") (pinfunction "2_2") (pintype "passive"))
      (node (ref "U5") (pin "4") (pinfunction "INNL_4") (pintype "passive"))
    )
    (net (code "53") (name "Net-(U5-INNR)") (class "Default")
      (node (ref "R54") (pin "2") (pinfunction "2_2") (pintype "passive"))
      (node (ref "U5") (pin "6") (pinfunction "INNR_6") (pintype "passive"))
    )
    (net (code "54") (name "Net-(U5-INPL)") (class "Default")
      (node (ref "R59") (pin "2") (pinfunction "2_2") (pintype "passive"))
      (node (ref "U5") (pin "3") (pinfunction "INPL_3") (pintype "passive"))
    )
    (net (code "55") (name "Net-(U5-INPR)") (class "Default")
      (node (ref "R53") (pin "2") (pinfunction "2_2") (pintype "passive"))
      (node (ref "U5") (pin "7") (pinfunction "INPR_7") (pintype "passive"))
    )
    (net (code "56") (name "Net-(U5-OUTNL)") (class "Default")
      (node (ref "C20") (pin "1") (pinfunction "1_1") (pintype "passive"))
      (node (ref "L7") (pin "2") (pinfunction "2_2") (pintype "passive"))
      (node (ref "U5") (pin "13") (pinfunction "OUTNL_13") (pintype "passive"))
    )
    (net (code "57") (name "Net-(U5-OUTNR)") (class "Default")
      (node (ref "C21") (pin "1") (pinfunction "1_1") (pintype "passive"))
      (node (ref "L2") (pin "2") (pinfunction "2_2") (pintype "passive"))
      (node (ref "U5") (pin "12") (pinfunction "OUTNR_12") (pintype "passive"))
    )
    (net (code "58") (name "Net-(U5-OUTPL)") (class "Default")
      (node (ref "C17") (pin "1") (pinfunction "1_1") (pintype "passive"))
      (node (ref "L6") (pin "2") (pinfunction "2_2") (pintype "passive"))
      (node (ref "U5") (pin "15") (pinfunction "OUTPL_15") (pintype "passive"))
    )
    (net (code "59") (name "Net-(U5-OUTPR)") (class "Default")
      (node (ref "C31") (pin "1") (pinfunction "1_1") (pintype "passive"))
      (node (ref "L3") (pin "2") (pinfunction "2_2") (pintype "passive"))
      (node (ref "U5") (pin "10") (pinfunction "OUTPR_10") (pintype "passive"))
    )
    (net (code "60") (name "Net-(U5-PSPR)") (class "Default")
      (node (ref "C31") (pin "2") (pinfunction "2_2") (pintype "passive"))
      (node (ref "U5") (pin "9") (pinfunction "PSPR_9") (pintype "passive"))
    )
    (net (code "61") (name "Net-(U7-BSMNR)") (class "Default")
      (node (ref "C50") (pin "2") (pinfunction "2_2") (pintype "passive"))
      (node (ref "U7") (pin "11") (pinfunction "BSMNR_11") (pintype "passive"))
      (node (ref "U7") (pin "9") (pinfunction "PSPR_9") (pintype "passive"))
    )
    (net (code "62") (name "Net-(U7-BSNL)") (class "Default")
      (node (ref "C38") (pin "2") (pinfunction "2_2") (pintype "passive"))
      (node (ref "U7") (pin "14") (pinfunction "BSNL_14") (pintype "passive"))
      (node (ref "U7") (pin "16") (pinfunction "BSPL_16") (pintype "passive"))
    )
    (net (code "63") (name "Net-(U7-GVDD)") (class "Default")
      (node (ref "C45") (pin "2") (pinfunction "2_2") (pintype "passive"))
      (node (ref "U7") (pin "5") (pinfunction "GVDD_5") (pintype "passive"))
    )
    (net (code "64") (name "Net-(U7-INNR)") (class "Default")
      (node (ref "R22") (pin "2") (pinfunction "2_2") (pintype "passive"))
      (node (ref "U7") (pin "6") (pinfunction "INNR_6") (pintype "passive"))
    )
    (net (code "65") (name "Net-(U7-INPR)") (class "Default")
      (node (ref "R21") (pin "2") (pinfunction "2_2") (pintype "passive"))
      (node (ref "U7") (pin "7") (pinfunction "INPR_7") (pintype "passive"))
    )
    (net (code "66") (name "Net-(U7-OUTNL)") (class "Default")
      (node (ref "C38") (pin "1") (pinfunction "1_1") (pintype "passive"))
      (node (ref "L4") (pin "2") (pinfunction "2_2") (pintype "passive"))
      (node (ref "U7") (pin "13") (pinfunction "OUTNL_13") (pintype "passive"))
      (node (ref "U7") (pin "15") (pinfunction "OUTPL_15") (pintype "passive"))
    )
    (net (code "67") (name "Net-(U7-OUTNR)") (class "Default")
      (node (ref "C50") (pin "1") (pinfunction "1_1") (pintype "passive"))
      (node (ref "L5") (pin "2") (pinfunction "2_2") (pintype "passive"))
      (node (ref "U7") (pin "10") (pinfunction "OUTPR_10") (pintype "passive"))
      (node (ref "U7") (pin "12") (pinfunction "OUTNR_12") (pintype "passive"))
    )
    (net (code "68") (name "Net-(U9-1IN+)") (class "Default")
      (node (ref "R16") (pin "1") (pinfunction "1_1") (pintype "passive"))
      (node (ref "R51") (pin "2") (pinfunction "2_2") (pintype "passive"))
      (node (ref "R67") (pin "1") (pinfunction "1_1") (pintype "passive"))
      (node (ref "U9") (pin "1") (pinfunction "1IN+_1") (pintype "passive"))
    )
    (net (code "69") (name "Net-(U9-1IN-)") (class "Default")
      (node (ref "R56") (pin "2") (pinfunction "2_2") (pintype "passive"))
      (node (ref "R62") (pin "1") (pinfunction "1_1") (pintype "passive"))
      (node (ref "R68") (pin "2") (pinfunction "2_2") (pintype "passive"))
      (node (ref "U9") (pin "3") (pinfunction "1IN-_3") (pintype "passive"))
    )
    (net (code "70") (name "Net-(U9-1OUT)") (class "Default")
      (node (ref "R20") (pin "1") (pinfunction "1_1") (pintype "passive"))
      (node (ref "R67") (pin "2") (pinfunction "2_2") (pintype "passive"))
      (node (ref "U9") (pin "4") (pinfunction "1OUT_4") (pintype "passive"))
    )
    (net (code "71") (name "VCC") (class "Default")
      (node (ref "C12") (pin "2") (pinfunction "2_2") (pintype "passive"))
      (node (ref "C13") (pin "1") (pinfunction "1_1") (pintype "passive"))
      (node (ref "C14") (pin "1") (pinfunction "POS_1") (pintype "passive"))
      (node (ref "C16") (pin "2") (pinfunction "2_2") (pintype "passive"))
      (node (ref "C22") (pin "1") (pinfunction "1_1") (pintype "passive"))
      (node (ref "C24") (pin "1") (pinfunction "1_1") (pintype "passive"))
      (node (ref "C25") (pin "1") (pinfunction "POS_1") (pintype "passive"))
      (node (ref "C26") (pin "2") (pinfunction "2_2") (pintype "passive"))
      (node (ref "C27") (pin "1") (pinfunction "POS_1") (pintype "passive"))
      (node (ref "C28") (pin "1") (pinfunction "POS_1") (pintype "passive"))
      (node (ref "C53") (pin "1") (pinfunction "POS_1") (pintype "passive"))
      (node (ref "C55") (pin "2") (pinfunction "2_2") (pintype "passive"))
      (node (ref "C56") (pin "1") (pinfunction "1_1") (pintype "passive"))
      (node (ref "C6") (pin "1") (pinfunction "1_1") (pintype "passive"))
      (node (ref "J5") (pin "1") (pinfunction "1_1") (pintype "passive"))
      (node (ref "U5") (pin "1") (pinfunction "PVCC_1") (pintype "passive"))
      (node (ref "U5") (pin "8") (pinfunction "PVCC_8") (pintype "passive"))
      (node (ref "U7") (pin "1") (pinfunction "PVCC_1") (pintype "passive"))
      (node (ref "U7") (pin "8") (pinfunction "PVCC_8") (pintype "passive"))
    )
    (net (code "72") (name "unconnected-(U10-+-Pad1)") (class "Default")
      (node (ref "U10") (pin "1") (pinfunction "+_1") (pintype "passive"))
    )
    (net (code "73") (name "unconnected-(U10---Pad2)") (class "Default")
      (node (ref "U10") (pin "2") (pinfunction "-_2") (pintype "passive"))
    )
  )
)
